# power.net
KiCad netlist of a schematic drawn in Altium Designer
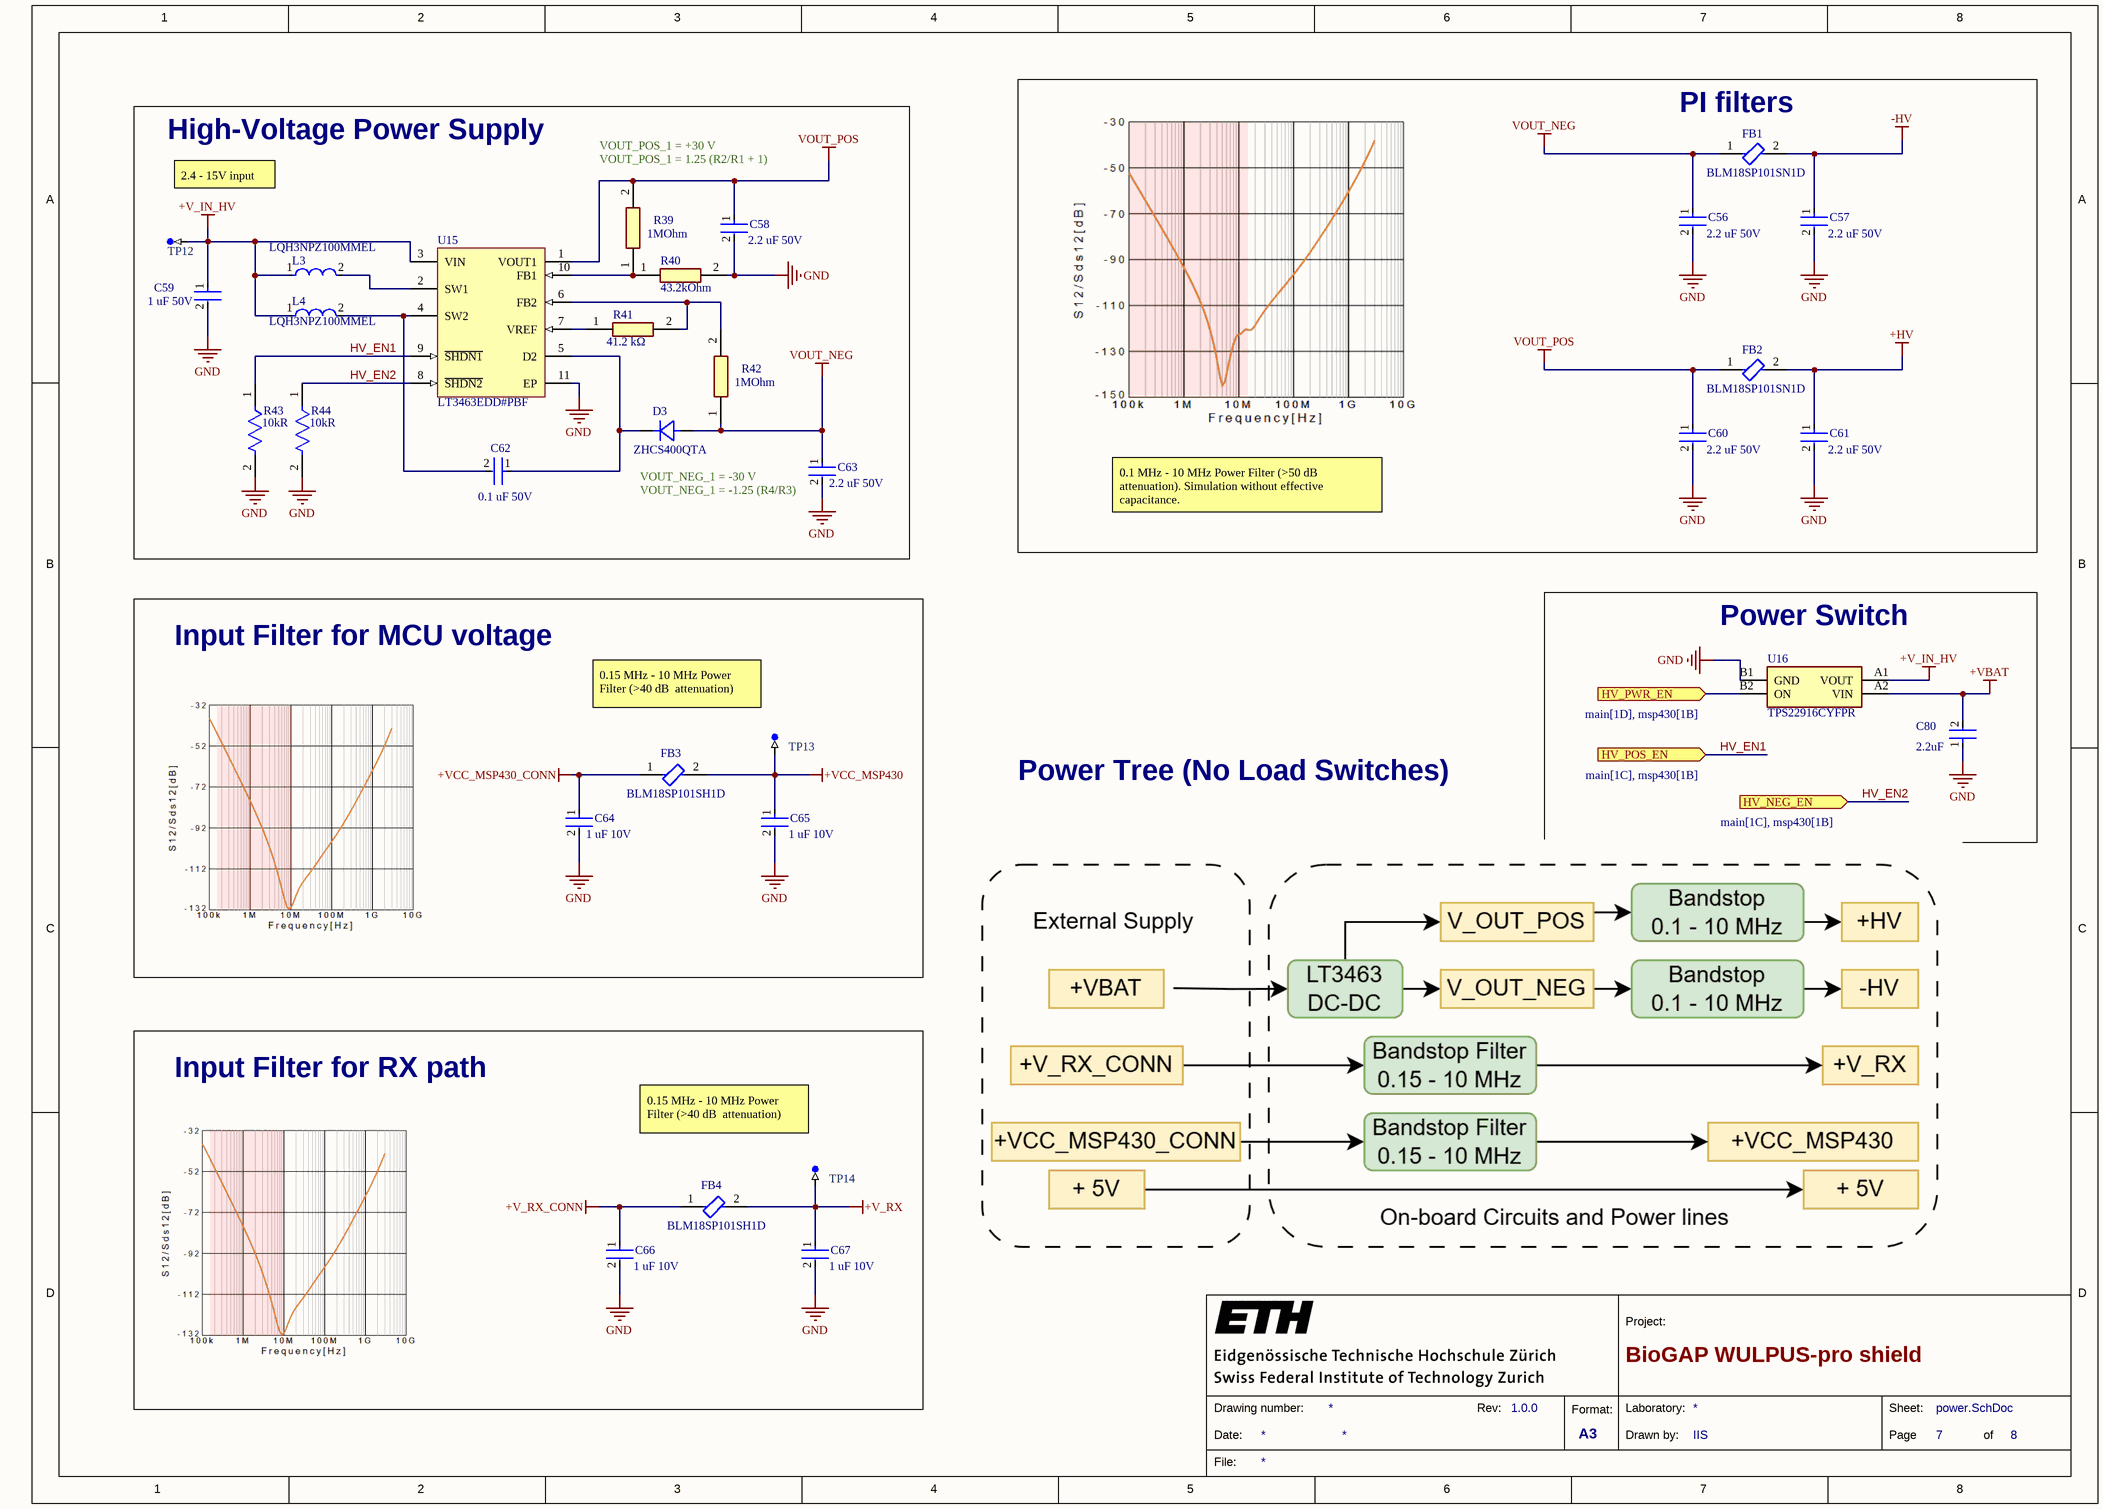
[diagram p0: power.SchDoc]

(export (version "E")
  (design (tool "Eeschema 10.0.6"))
  (components
    (comp (ref "C56")
      (value "GRM188R61H225ME11D")
      (footprint "FP-GRM188-0_2-IPC_B")
      (fields (field (name "CAPACITANCE") "2.2 uF 50V") (field (name "TOLERANCE") "20%"))
      (libsource (lib "Altium Content Vault") (part "11868f565c42a9108669ba33697ecf6"))
    )
    (comp (ref "C57")
      (value "GRM188R61H225ME11D")
      (footprint "FP-GRM188-0_2-IPC_B")
      (fields (field (name "CAPACITANCE") "2.2 uF 50V") (field (name "TOLERANCE") "20%"))
      (libsource (lib "Altium Content Vault") (part "11868f565c42a9108669ba33697ecf6"))
    )
    (comp (ref "C58")
      (value "GRM188R61H225ME11D")
      (footprint "FP-GRM188-0_2-IPC_B")
      (fields (field (name "CAPACITANCE") "2.2 uF 50V") (field (name "TOLERANCE") "20%"))
      (libsource (lib "Altium Content Vault") (part "11868f565c42a9108669ba33697ecf6"))
    )
    (comp (ref "C59")
      (value "GCM21BR71H105KA03L")
      (footprint "FP-GCM21B-0_15-IPC_C")
      (fields (field (name "CAPACITANCE") "1 uF 50V") (field (name "TOLERANCE") "10%"))
      (libsource (lib "Altium Content Vault") (part "02cd4be3c70576c341d710602a673aa"))
    )
    (comp (ref "C60")
      (value "GRM188R61H225ME11D")
      (footprint "FP-GRM188-0_2-IPC_B")
      (fields (field (name "CAPACITANCE") "2.2 uF 50V") (field (name "TOLERANCE") "20%"))
      (libsource (lib "Altium Content Vault") (part "11868f565c42a9108669ba33697ecf6"))
    )
    (comp (ref "C61")
      (value "GRM188R61H225ME11D")
      (footprint "FP-GRM188-0_2-IPC_B")
      (fields (field (name "CAPACITANCE") "2.2 uF 50V") (field (name "TOLERANCE") "20%"))
      (libsource (lib "Altium Content Vault") (part "11868f565c42a9108669ba33697ecf6"))
    )
    (comp (ref "C62")
      (value "GRM155C71H104KE19D")
      (footprint "FP-GRM155-0_05-MFG")
      (fields (field (name "TOLERANCE") "10%") (field (name "CAPACITANCE") "0.1 uF 50V"))
      (libsource (lib "Altium Content Vault") (part "02cd4be3c70576c341d710602a673aa"))
    )
    (comp (ref "C63")
      (value "GRM188R61H225ME11D")
      (footprint "FP-GRM188-0_2-IPC_B")
      (fields (field (name "CAPACITANCE") "2.2 uF 50V") (field (name "TOLERANCE") "20%"))
      (libsource (lib "Altium Content Vault") (part "11868f565c42a9108669ba33697ecf6"))
    )
    (comp (ref "C64")
      (value "GRM155Z71A105KE01D")
      (footprint "FP-GRM155-0_1-IPC_C")
      (fields (field (name "CAP") "1 uF 10V"))
      (libsource (lib "Altium Content Vault") (part "11868f565c42a9108669ba33697ecf6"))
    )
    (comp (ref "C65")
      (value "GRM155Z71A105KE01D")
      (footprint "FP-GRM155-0_1-IPC_C")
      (fields (field (name "CAP") "1 uF 10V"))
      (libsource (lib "Altium Content Vault") (part "11868f565c42a9108669ba33697ecf6"))
    )
    (comp (ref "C66")
      (value "GRM155Z71A105KE01D")
      (footprint "FP-GRM155-0_1-IPC_C")
      (fields (field (name "CAP") "1 uF 10V"))
      (libsource (lib "Altium Content Vault") (part "11868f565c42a9108669ba33697ecf6"))
    )
    (comp (ref "C67")
      (value "GRM155Z71A105KE01D")
      (footprint "FP-GRM155-0_1-IPC_C")
      (fields (field (name "CAP") "1 uF 10V"))
      (libsource (lib "Altium Content Vault") (part "11868f565c42a9108669ba33697ecf6"))
    )
    (comp (ref "C80")
      (value "C1005X7S1A225K050BC")
      (footprint "FP-C1005-050-0_15-0_1-MFG")
      (fields (field (name "CAPACITANCE") "2.2uF") (field (name "TOLERANCE") "10%"))
      (libsource (lib "Altium Content Vault") (part "b4654b650e69147ec39a6b967a45e02"))
    )
    (comp (ref "D3")
      (value "ZHCS400QTA")
      (footprint "DIODE_SOD323_DIO")
      (description "Diode Schottky 40V 1A Automotive 2-Pin SOD-323 T/R")
      (fields (field (name "MANUFACTURER") "Diodes"))
      (libsource (lib "Schlib1") (part "ZHCS400QTA"))
    )
    (comp (ref "FB1")
      (value "BLM18SP101SN1D")
      (footprint "FP-BLM18-0_15-t0_8-MFG")
      (description "BLM18SP101SN1D Ferrite Bead, 100 Ohm, 3.7A, 0603 Rohs Compliant: Yes")
      (fields (field (name "TOLERANCE") "25%"))
      (libsource (lib "Altium Content Vault") (part "5f30dd21d616792df468990f7003faa"))
    )
    (comp (ref "FB2")
      (value "BLM18SP101SN1D")
      (footprint "FP-BLM18-0_15-t0_8-MFG")
      (description "BLM18SP101SN1D Ferrite Bead, 100 Ohm, 3.7A, 0603 Rohs Compliant: Yes")
      (fields (field (name "TOLERANCE") "25%"))
      (libsource (lib "Altium Content Vault") (part "5f30dd21d616792df468990f7003faa"))
    )
    (comp (ref "FB3")
      (value "BLM18SP101SH1D")
      (footprint "FP-BLM18-0_15-t0_8-MFG")
      (description "BLM18SP101SH1D Ferrite Beads Multi-Layer 100Ohm 25% 100MHz 3.7A 0.022Ohm DCR 0603 Automotive T/R")
      (fields (field (name "TOLERANCE") "25%"))
      (libsource (lib "Altium Content Vault") (part "5f30dd21d616792df468990f7003faa"))
    )
    (comp (ref "FB4")
      (value "BLM18SP101SH1D")
      (footprint "FP-BLM18-0_15-t0_8-MFG")
      (description "BLM18SP101SH1D Ferrite Beads Multi-Layer 100Ohm 25% 100MHz 3.7A 0.022Ohm DCR 0603 Automotive T/R")
      (fields (field (name "TOLERANCE") "25%"))
      (libsource (lib "Altium Content Vault") (part "5f30dd21d616792df468990f7003faa"))
    )
    (comp (ref "L3")
      (value "LQH3NPZ100MMEL")
      (footprint "FP-LQH3NPH_ME-MFG")
      (description "Wire Wound Ferrite Inductor for Power Lines For Automotive 10μH ±20% 0.228Ω 1280mA 1212")
      (fields (field (name "TOLERANCE") "20%"))
      (libsource (lib "Altium Content Vault") (part "725321dda6339637d4d059423bc1c3c"))
    )
    (comp (ref "L4")
      (value "LQH3NPZ100MMEL")
      (footprint "FP-LQH3NPH_ME-MFG")
      (description "Wire Wound Ferrite Inductor for Power Lines For Automotive 10μH ±20% 0.228Ω 1280mA 1212")
      (fields (field (name "TOLERANCE") "20%"))
      (libsource (lib "Altium Content Vault") (part "725321dda6339637d4d059423bc1c3c"))
    )
    (comp (ref "R39")
      (value "ERJ-2RKF1004X")
      (footprint "SamacSys:ERJ2RKD1004X")
      (fields (field (name "MOUSER PART NUMBER") "667-ERJ-2RKF1004X") (field (name "RESISTANCE") "1MOhm"))
      (libsource (lib "*") (part "ERJ-2RKF1004X"))
    )
    (comp (ref "R40")
      (value "ERJ-2RKF4322X")
      (footprint "SamacSys:ERJ2RKD1004X")
      (fields (field (name "MOUSER PART NUMBER") "667-ERJ-2RKF4322X") (field (name "RESISTANCE") "43.2kOhm"))
      (libsource (lib "SamacSys") (part "ERJ-2RKF4322X"))
    )
    (comp (ref "R41")
      (value "ERJ-2RKF4122X")
      (footprint "SamacSys:ERJ2RKD1004X")
      (fields (field (name "MOUSER PART NUMBER") "667-ERJ-2RKF4122X") (field (name "RESISTANCE") "41.2 kΩ"))
      (libsource (lib "SamacSys") (part "ERJ-2RKF4122X"))
    )
    (comp (ref "R42")
      (value "ERJ-2RKF1004X")
      (footprint "SamacSys:ERJ2RKD1004X")
      (fields (field (name "MOUSER PART NUMBER") "667-ERJ-2RKF1004X") (field (name "RESISTANCE") "1MOhm"))
      (libsource (lib "*") (part "ERJ-2RKF1004X"))
    )
    (comp (ref "R43")
      (value "CRCW040210K0JNED")
      (footprint "FP-CRCW0402-e3-IPC_B")
      (fields (field (name "RESISTANCE") "10kR") (field (name "TOLERANCE") "5%"))
      (libsource (lib "Altium Content Vault") (part "1029c3af85768c4190bb7ad29bc67b5"))
    )
    (comp (ref "R44")
      (value "CRCW040210K0JNED")
      (footprint "FP-CRCW0402-e3-IPC_B")
      (fields (field (name "RESISTANCE") "10kR") (field (name "TOLERANCE") "5%"))
      (libsource (lib "Altium Content Vault") (part "1029c3af85768c4190bb7ad29bc67b5"))
    )
    (comp (ref "TP12")
      (value "TP-SM-C-100")
      (footprint "TP-SM-C-100")
      (description "Test Point, Surface Mount, Circular, Pad Diameter 1 mm")
      (libsource (lib "wulpus") (part "CMP-0484-00002-1"))
    )
    (comp (ref "TP13")
      (value "TP-SM-C-100")
      (footprint "TP-SM-C-100")
      (description "Test Point, Surface Mount, Circular, Pad Diameter 1 mm")
      (libsource (lib "wulpus") (part "CMP-0484-00002-1"))
    )
    (comp (ref "TP14")
      (value "TP-SM-C-100")
      (footprint "TP-SM-C-100")
      (description "Test Point, Surface Mount, Circular, Pad Diameter 1 mm")
      (libsource (lib "wulpus") (part "CMP-0484-00002-1"))
    )
    (comp (ref "U15")
      (value "LT3463EDD#PBF")
      (footprint "LT-DD-10_V")
      (fields (field (name "PARTNUMBER") "LT3463AEDD#PBF") (field (name "MANUFACTURER") "Linear Technology"))
      (libsource (lib "Altium Content Vault") (part "LT-LT3463A-DD-10"))
    )
    (comp (ref "U16")
      (value "TPS22916CYFPR")
      (footprint "BGA4C40P2X2_78X78X50")
      (description "TPS22916 5.5-V, 2-A Ultra-Low Leakage Load Switch")
      (libsource (lib "TPS22916CYFPR") (part "TPS22916CYFPR"))
    )
  )
  (nets
    (net (code "1") (name "+HV") (class "Default")
      (node (ref "C61") (pin "1") (pinfunction "1_1") (pintype "passive"))
      (node (ref "FB2") (pin "2") (pinfunction "2_2") (pintype "passive"))
    )
    (net (code "2") (name "+VBAT") (class "Default")
      (node (ref "C80") (pin "2") (pinfunction "2_2") (pintype "passive"))
      (node (ref "U16") (pin "A2") (pinfunction "VIN_A2") (pintype "passive"))
    )
    (net (code "3") (name "+VCC_MSP430") (class "Default")
      (node (ref "C65") (pin "1") (pinfunction "1_1") (pintype "passive"))
      (node (ref "FB3") (pin "2") (pinfunction "2_2") (pintype "passive"))
      (node (ref "TP13") (pin "1") (pinfunction "1_1") (pintype "input"))
    )
    (net (code "4") (name "+VCC_MSP430_CONN") (class "Default")
      (node (ref "C64") (pin "1") (pinfunction "1_1") (pintype "passive"))
      (node (ref "FB3") (pin "1") (pinfunction "1_1") (pintype "passive"))
    )
    (net (code "5") (name "+V_IN_HV") (class "Default")
      (node (ref "C59") (pin "1") (pinfunction "1_1") (pintype "passive"))
      (node (ref "L3") (pin "1") (pinfunction "1_1") (pintype "passive"))
      (node (ref "L4") (pin "1") (pinfunction "1_1") (pintype "passive"))
      (node (ref "TP12") (pin "1") (pinfunction "1_1") (pintype "input"))
      (node (ref "U15") (pin "3") (pinfunction "VIN_3") (pintype "power_in"))
      (node (ref "U16") (pin "A1") (pinfunction "VOUT_A1") (pintype "passive"))
    )
    (net (code "6") (name "+V_RX") (class "Default")
      (node (ref "C67") (pin "1") (pinfunction "1_1") (pintype "passive"))
      (node (ref "FB4") (pin "2") (pinfunction "2_2") (pintype "passive"))
      (node (ref "TP14") (pin "1") (pinfunction "1_1") (pintype "input"))
    )
    (net (code "7") (name "+V_RX_CONN") (class "Default")
      (node (ref "C66") (pin "1") (pinfunction "1_1") (pintype "passive"))
      (node (ref "FB4") (pin "1") (pinfunction "1_1") (pintype "passive"))
    )
    (net (code "8") (name "-HV") (class "Default")
      (node (ref "C57") (pin "1") (pinfunction "1_1") (pintype "passive"))
      (node (ref "FB1") (pin "2") (pinfunction "2_2") (pintype "passive"))
    )
    (net (code "9") (name "/HV_EN1") (class "Default")
      (node (ref "R43") (pin "1") (pinfunction "1_1") (pintype "passive"))
      (node (ref "U15") (pin "9") (pinfunction "~{SHDN1}_9") (pintype "input"))
    )
    (net (code "10") (name "/HV_EN2") (class "Default")
      (node (ref "R44") (pin "1") (pinfunction "1_1") (pintype "passive"))
      (node (ref "U15") (pin "8") (pinfunction "~{SHDN2}_8") (pintype "input"))
    )
    (net (code "11") (name "/HV_PWR_EN") (class "Default")
      (node (ref "U16") (pin "B2") (pinfunction "ON_B2") (pintype "passive"))
    )
    (net (code "12") (name "GND") (class "Default")
      (node (ref "C56") (pin "2") (pinfunction "2_2") (pintype "passive"))
      (node (ref "C57") (pin "2") (pinfunction "2_2") (pintype "passive"))
      (node (ref "C58") (pin "2") (pinfunction "2_2") (pintype "passive"))
      (node (ref "C59") (pin "2") (pinfunction "2_2") (pintype "passive"))
      (node (ref "C60") (pin "2") (pinfunction "2_2") (pintype "passive"))
      (node (ref "C61") (pin "2") (pinfunction "2_2") (pintype "passive"))
      (node (ref "C63") (pin "2") (pinfunction "2_2") (pintype "passive"))
      (node (ref "C64") (pin "2") (pinfunction "2_2") (pintype "passive"))
      (node (ref "C65") (pin "2") (pinfunction "2_2") (pintype "passive"))
      (node (ref "C66") (pin "2") (pinfunction "2_2") (pintype "passive"))
      (node (ref "C67") (pin "2") (pinfunction "2_2") (pintype "passive"))
      (node (ref "C80") (pin "1") (pinfunction "1_1") (pintype "passive"))
      (node (ref "R40") (pin "2") (pinfunction "2_2") (pintype "passive"))
      (node (ref "R43") (pin "2") (pinfunction "2_2") (pintype "passive"))
      (node (ref "R44") (pin "2") (pinfunction "2_2") (pintype "passive"))
      (node (ref "U15") (pin "11") (pinfunction "EP_11") (pintype "power_in"))
      (node (ref "U16") (pin "B1") (pinfunction "GND_B1") (pintype "passive"))
    )
    (net (code "13") (name "Net-(U15-D2)") (class "Default")
      (node (ref "C62") (pin "1") (pinfunction "1_1") (pintype "passive"))
      (node (ref "D3") (pin "1") (pinfunction "1_1") (pintype "passive"))
      (node (ref "U15") (pin "5") (pinfunction "D2_5") (pintype "passive"))
    )
    (net (code "14") (name "Net-(U15-FB1)") (class "Default")
      (node (ref "R39") (pin "1") (pinfunction "1_1") (pintype "passive"))
      (node (ref "R40") (pin "1") (pinfunction "1_1") (pintype "passive"))
      (node (ref "U15") (pin "10") (pinfunction "FB1_10") (pintype "input"))
    )
    (net (code "15") (name "Net-(U15-FB2)") (class "Default")
      (node (ref "R41") (pin "2") (pinfunction "2_2") (pintype "passive"))
      (node (ref "R42") (pin "2") (pinfunction "2_2") (pintype "passive"))
      (node (ref "U15") (pin "6") (pinfunction "FB2_6") (pintype "input"))
    )
    (net (code "16") (name "Net-(U15-SW1)") (class "Default")
      (node (ref "L3") (pin "2") (pinfunction "2_2") (pintype "passive"))
      (node (ref "U15") (pin "2") (pinfunction "SW1_2") (pintype "passive"))
    )
    (net (code "17") (name "Net-(U15-SW2)") (class "Default")
      (node (ref "C62") (pin "2") (pinfunction "2_2") (pintype "passive"))
      (node (ref "L4") (pin "2") (pinfunction "2_2") (pintype "passive"))
      (node (ref "U15") (pin "4") (pinfunction "SW2_4") (pintype "passive"))
    )
    (net (code "18") (name "Net-(U15-VREF)") (class "Default")
      (node (ref "R41") (pin "1") (pinfunction "1_1") (pintype "passive"))
      (node (ref "U15") (pin "7") (pinfunction "VREF_7") (pintype "input"))
    )
    (net (code "19") (name "VOUT_NEG") (class "Default")
      (node (ref "C56") (pin "1") (pinfunction "1_1") (pintype "passive"))
      (node (ref "C63") (pin "1") (pinfunction "1_1") (pintype "passive"))
      (node (ref "D3") (pin "2") (pinfunction "2_2") (pintype "passive"))
      (node (ref "FB1") (pin "1") (pinfunction "1_1") (pintype "passive"))
      (node (ref "R42") (pin "1") (pinfunction "1_1") (pintype "passive"))
    )
    (net (code "20") (name "VOUT_POS") (class "Default")
      (node (ref "C58") (pin "1") (pinfunction "1_1") (pintype "passive"))
      (node (ref "C60") (pin "1") (pinfunction "1_1") (pintype "passive"))
      (node (ref "FB2") (pin "1") (pinfunction "1_1") (pintype "passive"))
      (node (ref "R39") (pin "2") (pinfunction "2_2") (pintype "passive"))
      (node (ref "U15") (pin "1") (pinfunction "VOUT1_1") (pintype "power_in"))
    )
  )
)
